# DIYmakey_v2.net
KiCad netlist of a schematic drawn in EAGLE
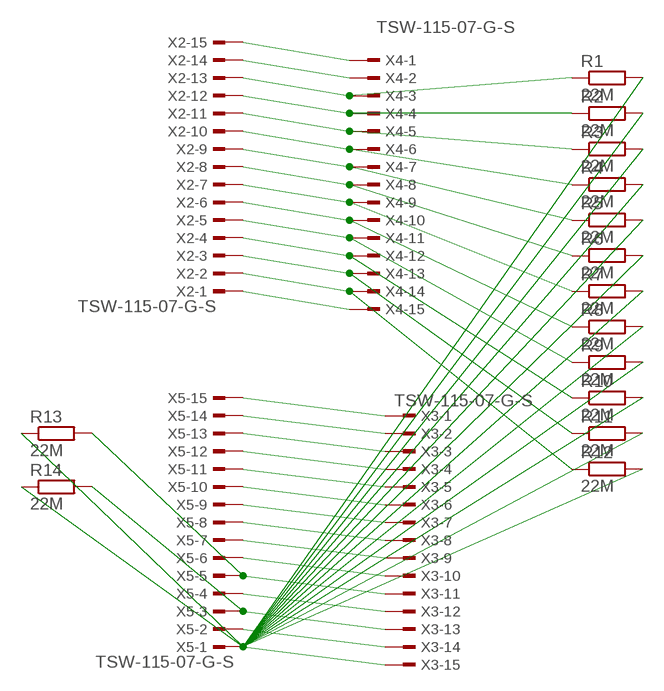
[diagram p0: schematic, sheet 1]

(export (version "E")
  (design (tool "Eeschema 10.0.6"))
  (components
    (comp (ref "R1")
      (value "22M")
      (footprint "eagle-import:0207_7")
      (libsource (lib "eagle-import") (part "R-EU_0207/7"))
    )
    (comp (ref "R2")
      (value "22M")
      (footprint "eagle-import:0207_7")
      (libsource (lib "eagle-import") (part "R-EU_0207/7"))
    )
    (comp (ref "R3")
      (value "22M")
      (footprint "eagle-import:0207_7")
      (libsource (lib "eagle-import") (part "R-EU_0207/7"))
    )
    (comp (ref "R4")
      (value "22M")
      (footprint "eagle-import:0207_7")
      (libsource (lib "eagle-import") (part "R-EU_0207/7"))
    )
    (comp (ref "R5")
      (value "22M")
      (footprint "eagle-import:0207_7")
      (libsource (lib "eagle-import") (part "R-EU_0207/7"))
    )
    (comp (ref "R6")
      (value "22M")
      (footprint "eagle-import:0207_7")
      (libsource (lib "eagle-import") (part "R-EU_0207/7"))
    )
    (comp (ref "R7")
      (value "22M")
      (footprint "eagle-import:0207_7")
      (libsource (lib "eagle-import") (part "R-EU_0207/7"))
    )
    (comp (ref "R8")
      (value "22M")
      (footprint "eagle-import:0207_7")
      (libsource (lib "eagle-import") (part "R-EU_0207/7"))
    )
    (comp (ref "R9")
      (value "22M")
      (footprint "eagle-import:0207_7")
      (libsource (lib "eagle-import") (part "R-EU_0207/7"))
    )
    (comp (ref "R10")
      (value "22M")
      (footprint "eagle-import:0207_7")
      (libsource (lib "eagle-import") (part "R-EU_0207/7"))
    )
    (comp (ref "R11")
      (value "22M")
      (footprint "eagle-import:0207_7")
      (libsource (lib "eagle-import") (part "R-EU_0207/7"))
    )
    (comp (ref "R12")
      (value "22M")
      (footprint "eagle-import:0207_7")
      (libsource (lib "eagle-import") (part "R-EU_0207/7"))
    )
    (comp (ref "R13")
      (value "22M")
      (footprint "eagle-import:0207_7")
      (libsource (lib "eagle-import") (part "R-EU_0207/7"))
    )
    (comp (ref "R14")
      (value "22M")
      (footprint "eagle-import:0207_7")
      (libsource (lib "eagle-import") (part "R-EU_0207/7"))
    )
    (comp (ref "X2")
      (value "TSW-115-07-G-S")
      (footprint "eagle-import:TSW-115-XX-G-S")
      (fields (field (name "MF") "Samtec Inc."))
      (libsource (lib "eagle-import") (part "TSW-115--G-S07"))
    )
    (comp (ref "X3")
      (value "TSW-115-07-G-S")
      (footprint "eagle-import:TSW-115-XX-G-S")
      (fields (field (name "MF") "Samtec Inc."))
      (libsource (lib "eagle-import") (part "TSW-115--G-S07"))
    )
    (comp (ref "X4")
      (value "TSW-115-07-G-S")
      (footprint "eagle-import:TSW-115-XX-G-S")
      (fields (field (name "MF") "Samtec Inc."))
      (libsource (lib "eagle-import") (part "TSW-115--G-S07"))
    )
    (comp (ref "X5")
      (value "TSW-115-07-G-S")
      (footprint "eagle-import:TSW-115-XX-G-S")
      (fields (field (name "MF") "Samtec Inc."))
      (libsource (lib "eagle-import") (part "TSW-115--G-S07"))
    )
  )
  (nets
    (net (code "1") (name "Net-(X2B-1)") (class "Default")
      (node (ref "R4") (pin "1") (pinfunction "1_1") (pintype "passive"))
      (node (ref "X2") (pin "10") (pinfunction "1_10") (pintype "passive"))
      (node (ref "X4") (pin "6") (pinfunction "1_6") (pintype "passive"))
    )
    (net (code "2") (name "Net-(X2C-1)") (class "Default")
      (node (ref "R3") (pin "1") (pinfunction "1_1") (pintype "passive"))
      (node (ref "X2") (pin "11") (pinfunction "1_11") (pintype "passive"))
      (node (ref "X4") (pin "5") (pinfunction "1_5") (pintype "passive"))
    )
    (net (code "3") (name "Net-(X2D-1)") (class "Default")
      (node (ref "R2") (pin "1") (pinfunction "1_1") (pintype "passive"))
      (node (ref "X2") (pin "12") (pinfunction "1_12") (pintype "passive"))
      (node (ref "X4") (pin "4") (pinfunction "1_4") (pintype "passive"))
    )
    (net (code "4") (name "Net-(X2E-1)") (class "Default")
      (node (ref "R1") (pin "1") (pinfunction "1_1") (pintype "passive"))
      (node (ref "X2") (pin "13") (pinfunction "1_13") (pintype "passive"))
      (node (ref "X4") (pin "3") (pinfunction "1_3") (pintype "passive"))
    )
    (net (code "5") (name "Net-(X2F-1)") (class "Default")
      (node (ref "X2") (pin "14") (pinfunction "1_14") (pintype "passive"))
      (node (ref "X4") (pin "2") (pinfunction "1_2") (pintype "passive"))
    )
    (net (code "6") (name "Net-(X2G-1)") (class "Default")
      (node (ref "X2") (pin "15") (pinfunction "1_15") (pintype "passive"))
      (node (ref "X4") (pin "1") (pinfunction "1_1") (pintype "passive"))
    )
    (net (code "7") (name "Net-(X2H-1)") (class "Default")
      (node (ref "R12") (pin "1") (pinfunction "1_1") (pintype "passive"))
      (node (ref "X2") (pin "2") (pinfunction "1_2") (pintype "passive"))
      (node (ref "X4") (pin "14") (pinfunction "1_14") (pintype "passive"))
    )
    (net (code "8") (name "Net-(X2I-1)") (class "Default")
      (node (ref "R11") (pin "1") (pinfunction "1_1") (pintype "passive"))
      (node (ref "X2") (pin "3") (pinfunction "1_3") (pintype "passive"))
      (node (ref "X4") (pin "13") (pinfunction "1_13") (pintype "passive"))
    )
    (net (code "9") (name "Net-(X2J-1)") (class "Default")
      (node (ref "R10") (pin "1") (pinfunction "1_1") (pintype "passive"))
      (node (ref "X2") (pin "4") (pinfunction "1_4") (pintype "passive"))
      (node (ref "X4") (pin "12") (pinfunction "1_12") (pintype "passive"))
    )
    (net (code "10") (name "Net-(X2K-1)") (class "Default")
      (node (ref "R9") (pin "1") (pinfunction "1_1") (pintype "passive"))
      (node (ref "X2") (pin "5") (pinfunction "1_5") (pintype "passive"))
      (node (ref "X4") (pin "11") (pinfunction "1_11") (pintype "passive"))
    )
    (net (code "11") (name "Net-(X2L-1)") (class "Default")
      (node (ref "R8") (pin "1") (pinfunction "1_1") (pintype "passive"))
      (node (ref "X2") (pin "6") (pinfunction "1_6") (pintype "passive"))
      (node (ref "X4") (pin "10") (pinfunction "1_10") (pintype "passive"))
    )
    (net (code "12") (name "Net-(X2M-1)") (class "Default")
      (node (ref "R7") (pin "1") (pinfunction "1_1") (pintype "passive"))
      (node (ref "X2") (pin "7") (pinfunction "1_7") (pintype "passive"))
      (node (ref "X4") (pin "9") (pinfunction "1_9") (pintype "passive"))
    )
    (net (code "13") (name "Net-(X2N-1)") (class "Default")
      (node (ref "R6") (pin "1") (pinfunction "1_1") (pintype "passive"))
      (node (ref "X2") (pin "8") (pinfunction "1_8") (pintype "passive"))
      (node (ref "X4") (pin "8") (pinfunction "1_8") (pintype "passive"))
    )
    (net (code "14") (name "Net-(X2O-1)") (class "Default")
      (node (ref "R5") (pin "1") (pinfunction "1_1") (pintype "passive"))
      (node (ref "X2") (pin "9") (pinfunction "1_9") (pintype "passive"))
      (node (ref "X4") (pin "7") (pinfunction "1_7") (pintype "passive"))
    )
    (net (code "15") (name "Net-(X3B-1)") (class "Default")
      (node (ref "X3") (pin "10") (pinfunction "1_10") (pintype "passive"))
      (node (ref "X5") (pin "6") (pinfunction "1_6") (pintype "passive"))
    )
    (net (code "16") (name "Net-(X3C-1)") (class "Default")
      (node (ref "R13") (pin "2") (pinfunction "2_2") (pintype "passive"))
      (node (ref "X3") (pin "11") (pinfunction "1_11") (pintype "passive"))
      (node (ref "X5") (pin "5") (pinfunction "1_5") (pintype "passive"))
    )
    (net (code "17") (name "Net-(X3D-1)") (class "Default")
      (node (ref "X3") (pin "12") (pinfunction "1_12") (pintype "passive"))
      (node (ref "X5") (pin "4") (pinfunction "1_4") (pintype "passive"))
    )
    (net (code "18") (name "Net-(X3E-1)") (class "Default")
      (node (ref "R14") (pin "2") (pinfunction "2_2") (pintype "passive"))
      (node (ref "X3") (pin "13") (pinfunction "1_13") (pintype "passive"))
      (node (ref "X5") (pin "3") (pinfunction "1_3") (pintype "passive"))
    )
    (net (code "19") (name "Net-(X3F-1)") (class "Default")
      (node (ref "X3") (pin "14") (pinfunction "1_14") (pintype "passive"))
      (node (ref "X5") (pin "2") (pinfunction "1_2") (pintype "passive"))
    )
    (net (code "20") (name "Net-(X3G-1)") (class "Default")
      (node (ref "R1") (pin "2") (pinfunction "2_2") (pintype "passive"))
      (node (ref "R10") (pin "2") (pinfunction "2_2") (pintype "passive"))
      (node (ref "R11") (pin "2") (pinfunction "2_2") (pintype "passive"))
      (node (ref "R12") (pin "2") (pinfunction "2_2") (pintype "passive"))
      (node (ref "R13") (pin "1") (pinfunction "1_1") (pintype "passive"))
      (node (ref "R14") (pin "1") (pinfunction "1_1") (pintype "passive"))
      (node (ref "R2") (pin "2") (pinfunction "2_2") (pintype "passive"))
      (node (ref "R3") (pin "2") (pinfunction "2_2") (pintype "passive"))
      (node (ref "R4") (pin "2") (pinfunction "2_2") (pintype "passive"))
      (node (ref "R5") (pin "2") (pinfunction "2_2") (pintype "passive"))
      (node (ref "R6") (pin "2") (pinfunction "2_2") (pintype "passive"))
      (node (ref "R7") (pin "2") (pinfunction "2_2") (pintype "passive"))
      (node (ref "R8") (pin "2") (pinfunction "2_2") (pintype "passive"))
      (node (ref "R9") (pin "2") (pinfunction "2_2") (pintype "passive"))
      (node (ref "X3") (pin "15") (pinfunction "1_15") (pintype "passive"))
      (node (ref "X5") (pin "1") (pinfunction "1_1") (pintype "passive"))
    )
    (net (code "21") (name "Net-(X3H-1)") (class "Default")
      (node (ref "X3") (pin "2") (pinfunction "1_2") (pintype "passive"))
      (node (ref "X5") (pin "14") (pinfunction "1_14") (pintype "passive"))
    )
    (net (code "22") (name "Net-(X3I-1)") (class "Default")
      (node (ref "X3") (pin "3") (pinfunction "1_3") (pintype "passive"))
      (node (ref "X5") (pin "13") (pinfunction "1_13") (pintype "passive"))
    )
    (net (code "23") (name "Net-(X3J-1)") (class "Default")
      (node (ref "X3") (pin "4") (pinfunction "1_4") (pintype "passive"))
      (node (ref "X5") (pin "12") (pinfunction "1_12") (pintype "passive"))
    )
    (net (code "24") (name "Net-(X3K-1)") (class "Default")
      (node (ref "X3") (pin "5") (pinfunction "1_5") (pintype "passive"))
      (node (ref "X5") (pin "11") (pinfunction "1_11") (pintype "passive"))
    )
    (net (code "25") (name "Net-(X3L-1)") (class "Default")
      (node (ref "X3") (pin "6") (pinfunction "1_6") (pintype "passive"))
      (node (ref "X5") (pin "10") (pinfunction "1_10") (pintype "passive"))
    )
    (net (code "26") (name "Net-(X3M-1)") (class "Default")
      (node (ref "X3") (pin "7") (pinfunction "1_7") (pintype "passive"))
      (node (ref "X5") (pin "9") (pinfunction "1_9") (pintype "passive"))
    )
    (net (code "27") (name "Net-(X3N-1)") (class "Default")
      (node (ref "X3") (pin "8") (pinfunction "1_8") (pintype "passive"))
      (node (ref "X5") (pin "8") (pinfunction "1_8") (pintype "passive"))
    )
    (net (code "28") (name "Net-(X3O-1)") (class "Default")
      (node (ref "X3") (pin "9") (pinfunction "1_9") (pintype "passive"))
      (node (ref "X5") (pin "7") (pinfunction "1_7") (pintype "passive"))
    )
    (net (code "29") (name "Net-(X4G-1)") (class "Default")
      (node (ref "X2") (pin "1") (pinfunction "1_1") (pintype "passive"))
      (node (ref "X4") (pin "15") (pinfunction "1_15") (pintype "passive"))
    )
    (net (code "30") (name "Net-(X5G-1)") (class "Default")
      (node (ref "X3") (pin "1") (pinfunction "1_1") (pintype "passive"))
      (node (ref "X5") (pin "15") (pinfunction "1_15") (pintype "passive"))
    )
  )
)
